# Baseband.net
KiCad netlist of a schematic drawn in Altium Designer
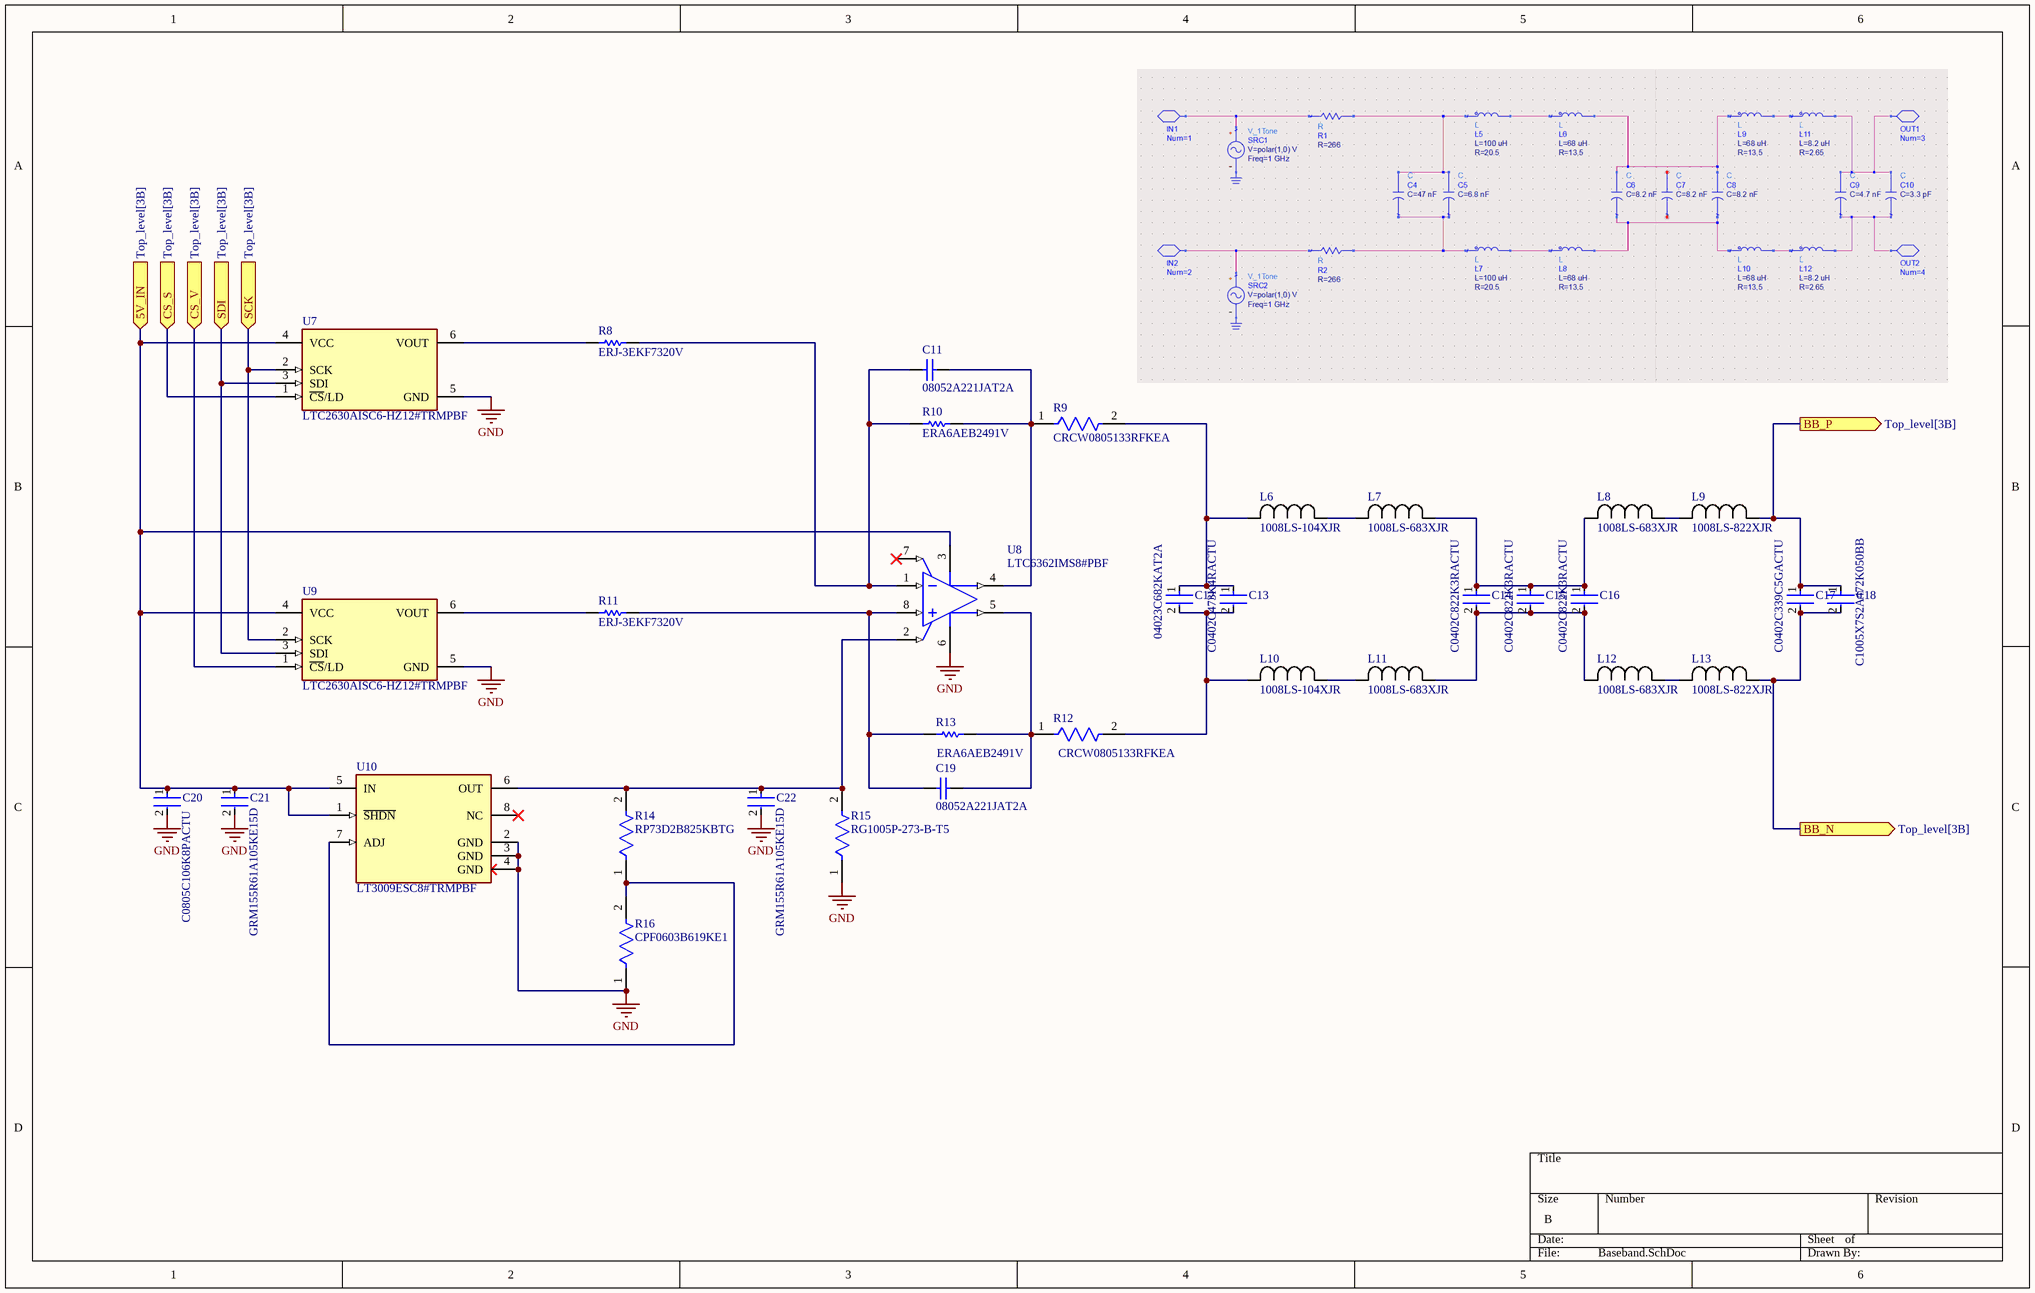
[diagram p0: Baseband.SchDoc]

(export (version "E")
  (design (tool "Eeschema 10.0.6"))
  (components
    (comp (ref "C11")
      (value "08052A221JAT2A")
      (footprint "CAPC2013X140X50LL20T25")
      (fields (field (name "MANUFACTURER") "AVX Interconnect / Elco"))
      (libsource (lib "Altium Content Vault") (part "CAP"))
    )
    (comp (ref "C12")
      (value "04023C682KAT2A")
      (footprint "FP-0402-L_1_0_1-W_0_5_0_1-IPC_A")
      (description "General Purpose Ceramic Capacitor, 0402, 6.8nF, 10%, X7R, 15%, 25V")
      (fields (field (name "TOLERANCE") "10%") (field (name "VOLTAGE") "25V"))
      (libsource (lib "Altium Content Vault") (part "b4654b650e69147ec39a6b967a45e02"))
    )
    (comp (ref "C13")
      (value "C0402C473K4RACTU")
      (footprint "FP-C0402-BB-MFG")
      (description "Cap Ceramic 0.047uF 16V X7R 10% SMD 0402 125°C Paper T/R")
      (fields (field (name "TOLERANCE") "0.1") (field (name "MANUFACTURER") "Kemet"))
      (libsource (lib "Altium Content Vault") (part "b4654b650e69147ec39a6b967a45e02"))
    )
    (comp (ref "C14")
      (value "C0402C822K3RACTU")
      (footprint "FP-C0402-BB-MFG")
      (description "CAP CER 8200PF 25V X7R 0402")
      (fields (field (name "TOLERANCE") "0.1") (field (name "MANUFACTURER") "Kemet"))
      (libsource (lib "Altium Content Vault") (part "b4654b650e69147ec39a6b967a45e02"))
    )
    (comp (ref "C15")
      (value "C0402C822K3RACTU")
      (footprint "FP-C0402-BB-MFG")
      (description "CAP CER 8200PF 25V X7R 0402")
      (fields (field (name "TOLERANCE") "0.1") (field (name "MANUFACTURER") "Kemet"))
      (libsource (lib "Altium Content Vault") (part "b4654b650e69147ec39a6b967a45e02"))
    )
    (comp (ref "C16")
      (value "C0402C822K3RACTU")
      (footprint "FP-C0402-BB-MFG")
      (description "CAP CER 8200PF 25V X7R 0402")
      (fields (field (name "TOLERANCE") "0.1") (field (name "MANUFACTURER") "Kemet"))
      (libsource (lib "Altium Content Vault") (part "b4654b650e69147ec39a6b967a45e02"))
    )
    (comp (ref "C17")
      (value "C1005X7S2A472K050BB")
      (footprint "FP-C1005-050-0_05-IPC_C")
      (description "Multilayer Ceramic Capacitors 4.7nF ±10% 100V X7S SMD 0402")
      (fields (field (name "TOLERANCE") "10%"))
      (libsource (lib "Altium Content Vault") (part "b4654b650e69147ec39a6b967a45e02"))
    )
    (comp (ref "C18")
      (value "C0402C339C5GACTU")
      (footprint "FP-C0402-BB-MFG")
      (description "Capacitor: ceramic; MLCC; 3.3pF; 50VDC; C0G; ±0.25pF; SMD; 0402")
      (fields (field (name "TOLERANCE") "0.25 pF") (field (name "MANUFACTURER") "Kemet"))
      (libsource (lib "Altium Content Vault") (part "b4654b650e69147ec39a6b967a45e02"))
    )
    (comp (ref "C19")
      (value "08052A221JAT2A")
      (footprint "CAPC2013X140X50LL20T25")
      (fields (field (name "MANUFACTURER") "AVX Interconnect / Elco"))
      (libsource (lib "Altium Content Vault") (part "CAP"))
    )
    (comp (ref "C20")
      (value "C0805C106K8PACTU")
      (footprint "FP-C0805C-DG-MFG")
      (description "CAP CER 10UF 10V X5R 0805")
      (fields (field (name "TOLERANCE") "10%") (field (name "MANUFACTURER") "Kemet"))
      (libsource (lib "Altium Content Vault") (part "11868f565c42a9108669ba33697ecf6"))
    )
    (comp (ref "C21")
      (value "GRM155R61A105KE15D")
      (footprint "FP-GRM15-0_1-MFG")
      (description "CAP CER 1UF 10V X5R 0402")
      (fields
        (field (name "OCTOPART") "https://octopart.com/grm155r61a105ke15d-murata-197442")
        (field (name "MANUFACTURER") "Murata")
      )
      (libsource (lib "Altium Content Vault") (part "02cd4be3c70576c341d710602a673aa"))
    )
    (comp (ref "C22")
      (value "GRM155R61A105KE15D")
      (footprint "FP-GRM15-0_1-MFG")
      (description "CAP CER 1UF 10V X5R 0402")
      (fields
        (field (name "OCTOPART") "https://octopart.com/grm155r61a105ke15d-murata-197442")
        (field (name "MANUFACTURER") "Murata")
      )
      (libsource (lib "Altium Content Vault") (part "02cd4be3c70576c341d710602a673aa"))
    )
    (comp (ref "L6")
      (value "1008LS-104XJR")
      (footprint "IND_1008LS")
      (description "No Description Available")
      (fields
        (field (name "MANUFACTURER_PART_NUMBER") "1008LS-152XJLC")
        (field (name "COPYRIGHT") "Copyright (C) 2023 Ultra Librarian. All rights reserved.")
      )
      (libsource (lib "1008LS-152XJLC") (part "1008LS-152XJLC"))
    )
    (comp (ref "L7")
      (value "1008LS-683XJR")
      (footprint "IND_1008LS")
      (description "No Description Available")
      (fields
        (field (name "MANUFACTURER_PART_NUMBER") "1008LS-152XJLC")
        (field (name "COPYRIGHT") "Copyright (C) 2023 Ultra Librarian. All rights reserved.")
      )
      (libsource (lib "1008LS-152XJLC") (part "1008LS-152XJLC"))
    )
    (comp (ref "L8")
      (value "1008LS-683XJR")
      (footprint "IND_1008LS")
      (description "No Description Available")
      (fields
        (field (name "MANUFACTURER_PART_NUMBER") "1008LS-152XJLC")
        (field (name "COPYRIGHT") "Copyright (C) 2023 Ultra Librarian. All rights reserved.")
      )
      (libsource (lib "1008LS-152XJLC") (part "1008LS-152XJLC"))
    )
    (comp (ref "L9")
      (value "1008LS-822XJR")
      (footprint "IND_1008LS")
      (description "No Description Available")
      (fields
        (field (name "MANUFACTURER_PART_NUMBER") "1008LS-152XJLC")
        (field (name "COPYRIGHT") "Copyright (C) 2023 Ultra Librarian. All rights reserved.")
      )
      (libsource (lib "1008LS-152XJLC") (part "1008LS-152XJLC"))
    )
    (comp (ref "L10")
      (value "1008LS-104XJR")
      (footprint "IND_1008LS")
      (description "No Description Available")
      (fields
        (field (name "MANUFACTURER_PART_NUMBER") "1008LS-152XJLC")
        (field (name "COPYRIGHT") "Copyright (C) 2023 Ultra Librarian. All rights reserved.")
      )
      (libsource (lib "1008LS-152XJLC") (part "1008LS-152XJLC"))
    )
    (comp (ref "L11")
      (value "1008LS-683XJR")
      (footprint "IND_1008LS")
      (description "No Description Available")
      (fields
        (field (name "MANUFACTURER_PART_NUMBER") "1008LS-152XJLC")
        (field (name "COPYRIGHT") "Copyright (C) 2023 Ultra Librarian. All rights reserved.")
      )
      (libsource (lib "1008LS-152XJLC") (part "1008LS-152XJLC"))
    )
    (comp (ref "L12")
      (value "1008LS-683XJR")
      (footprint "IND_1008LS")
      (description "No Description Available")
      (fields
        (field (name "MANUFACTURER_PART_NUMBER") "1008LS-152XJLC")
        (field (name "COPYRIGHT") "Copyright (C) 2023 Ultra Librarian. All rights reserved.")
      )
      (libsource (lib "1008LS-152XJLC") (part "1008LS-152XJLC"))
    )
    (comp (ref "L13")
      (value "1008LS-822XJR")
      (footprint "IND_1008LS")
      (description "No Description Available")
      (fields
        (field (name "MANUFACTURER_PART_NUMBER") "1008LS-152XJLC")
        (field (name "COPYRIGHT") "Copyright (C) 2023 Ultra Librarian. All rights reserved.")
      )
      (libsource (lib "1008LS-152XJLC") (part "1008LS-152XJLC"))
    )
    (comp (ref "R8")
      (value "ERJ-3EKF7320V")
      (footprint "RESC1608X55X30LL15T15")
      (fields (field (name "MANUFACTURER") "Panasonic"))
      (libsource (lib "Altium Content Vault") (part "RES"))
    )
    (comp (ref "R9")
      (value "CRCW0805133RFKEA")
      (footprint "FP-CRCW0805-e3-IPC_C")
      (description "RES Thick Film, 133Ω, 1%, 0.125W, 100ppm/°C, 0805")
      (fields (field (name "TOLERANCE") "1%"))
      (libsource (lib "Altium Content Vault") (part "1029c3af85768c4190bb7ad29bc67b5"))
    )
    (comp (ref "R10")
      (value "ERA6AEB2491V")
      (footprint "RESC2013X60X40LL20T25")
      (fields (field (name "MANUFACTURER") "Panasonic"))
      (libsource (lib "Altium Content Vault") (part "RES"))
    )
    (comp (ref "R11")
      (value "ERJ-3EKF7320V")
      (footprint "RESC1608X55X30LL15T15")
      (fields (field (name "MANUFACTURER") "Panasonic"))
      (libsource (lib "Altium Content Vault") (part "RES"))
    )
    (comp (ref "R12")
      (value "CRCW0805133RFKEA")
      (footprint "FP-CRCW0805-e3-IPC_C")
      (description "RES Thick Film, 133Ω, 1%, 0.125W, 100ppm/°C, 0805")
      (fields (field (name "TOLERANCE") "1%"))
      (libsource (lib "Altium Content Vault") (part "1029c3af85768c4190bb7ad29bc67b5"))
    )
    (comp (ref "R13")
      (value "ERA6AEB2491V")
      (footprint "RESC2013X60X40LL20T25")
      (fields (field (name "MANUFACTURER") "Panasonic"))
      (libsource (lib "Altium Content Vault") (part "RES"))
    )
    (comp (ref "R14")
      (value "RP73D2B825KBTG")
      (footprint "FP-RP732B-MFG")
      (description "Res Thin Film 1206 825KΩ 0.1% 0.25W 15ppm/°C Molded SMD")
      (fields
        (field (name "TOLERANCE") "0.1%")
        (field (name "OCTOPART") "https://octopart.com/rp73d2b825kbtg-te+connectivity-42012325")
      )
      (libsource (lib "Altium Content Vault") (part "1029c3af85768c4190bb7ad29bc67b5"))
    )
    (comp (ref "R15")
      (value "RG1005P-273-B-T5")
      (footprint "FP-RG1005-IPC_B")
      (description "Automotive Metal Thin Film Chip Resistor, 0402, 27kΩ, 0.1%, 25ppm/°C, 0.0625W, 75V")
      (fields (field (name "TOLERANCE") "0.1%"))
      (libsource (lib "Altium Content Vault") (part "1029c3af85768c4190bb7ad29bc67b5"))
    )
    (comp (ref "R16")
      (value "CPF0603B619KE1")
      (footprint "FP-CPF0603-MFG")
      (description "RES SMD 619KΩ 0.1% 1/16W 0603")
      (fields (field (name "TOLERANCE") "0.1%") (field (name "MANUFACTURER") "TE Connectivity"))
      (libsource (lib "Altium Content Vault") (part "1029c3af85768c4190bb7ad29bc67b5"))
    )
    (comp (ref "U7")
      (value "LTC2630AISC6-HZ12#TRMPBF")
      (footprint "FP-SC6-6-05-08-1638-IPC_A")
      (description "IC DAC 12BIT V-OUT SC70-6")
      (libsource (lib "Altium Content Vault") (part "11e261d70a0233db44de8961138878f"))
    )
    (comp (ref "U8")
      (value "LTC6362IMS8#PBF")
      (footprint "LT-MS8-8_L")
      (fields
        (field (name "MANUFACTURER") "Linear Technology")
        (field (name "LINEAR TECHNOLOGY PART NUMBER") "LTC6362")
      )
      (libsource (lib "Altium Content Vault") (part "LT-LTC6362-MS8-8"))
    )
    (comp (ref "U9")
      (value "LTC2630AISC6-HZ12#TRMPBF")
      (footprint "FP-SC6-6-05-08-1638-IPC_A")
      (description "IC DAC 12BIT V-OUT SC70-6")
      (libsource (lib "Altium Content Vault") (part "11e261d70a0233db44de8961138878f"))
    )
    (comp (ref "U10")
      (value "LT3009ESC8#TRMPBF")
      (footprint "FP-SC8-8-05-08-1639-MFG")
      (description "IC REG LIN POS ADJ 20MA SC70-8")
      (libsource (lib "Altium Content Vault") (part "448a231521b8ff0e769f98827e76e85"))
    )
  )
  (nets
    (net (code "1") (name "/5V_IN") (class "Default")
      (node (ref "C20") (pin "1") (pinfunction "1_1") (pintype "passive"))
      (node (ref "C21") (pin "1") (pinfunction "1_1") (pintype "passive"))
      (node (ref "U10") (pin "1") (pinfunction "~{SHDN}_1") (pintype "input"))
      (node (ref "U10") (pin "5") (pinfunction "IN_5") (pintype "power_in"))
      (node (ref "U7") (pin "4") (pinfunction "VCC_4") (pintype "power_in"))
      (node (ref "U8") (pin "3") (pinfunction "V+_3") (pintype "power_in"))
      (node (ref "U9") (pin "4") (pinfunction "VCC_4") (pintype "power_in"))
    )
    (net (code "2") (name "/BB_N") (class "Default")
      (node (ref "C17") (pin "2") (pinfunction "2_2") (pintype "passive"))
      (node (ref "C18") (pin "2") (pinfunction "2_2") (pintype "passive"))
      (node (ref "L13") (pin "1") (pinfunction "1_1") (pintype "passive"))
    )
    (net (code "3") (name "/BB_P") (class "Default")
      (node (ref "C17") (pin "1") (pinfunction "1_1") (pintype "passive"))
      (node (ref "C18") (pin "1") (pinfunction "1_1") (pintype "passive"))
      (node (ref "L9") (pin "1") (pinfunction "1_1") (pintype "passive"))
    )
    (net (code "4") (name "/CS_S") (class "Default")
      (node (ref "U7") (pin "1") (pinfunction "~{CS}/LD_1") (pintype "input"))
    )
    (net (code "5") (name "/CS_V") (class "Default")
      (node (ref "U9") (pin "1") (pinfunction "~{CS}/LD_1") (pintype "input"))
    )
    (net (code "6") (name "/SCK") (class "Default")
      (node (ref "U7") (pin "2") (pinfunction "SCK_2") (pintype "input"))
      (node (ref "U9") (pin "2") (pinfunction "SCK_2") (pintype "input"))
    )
    (net (code "7") (name "/SDI") (class "Default")
      (node (ref "U7") (pin "3") (pinfunction "SDI_3") (pintype "input"))
      (node (ref "U9") (pin "3") (pinfunction "SDI_3") (pintype "input"))
    )
    (net (code "8") (name "GND") (class "Default")
      (node (ref "C20") (pin "2") (pinfunction "2_2") (pintype "passive"))
      (node (ref "C21") (pin "2") (pinfunction "2_2") (pintype "passive"))
      (node (ref "C22") (pin "2") (pinfunction "2_2") (pintype "passive"))
      (node (ref "R15") (pin "1") (pinfunction "1_1") (pintype "passive"))
      (node (ref "R16") (pin "1") (pinfunction "1_1") (pintype "passive"))
      (node (ref "U10") (pin "2") (pinfunction "GND_2") (pintype "power_in"))
      (node (ref "U10") (pin "3") (pinfunction "GND_3") (pintype "power_in"))
      (node (ref "U10") (pin "4") (pinfunction "GND_4") (pintype "power_in"))
      (node (ref "U7") (pin "5") (pinfunction "GND_5") (pintype "power_in"))
      (node (ref "U8") (pin "6") (pinfunction "V-_6") (pintype "power_in"))
      (node (ref "U9") (pin "5") (pinfunction "GND_5") (pintype "power_in"))
    )
    (net (code "9") (name "Net-(C12-Pad1)") (class "Default")
      (node (ref "C12") (pin "1") (pinfunction "1_1") (pintype "passive"))
      (node (ref "C13") (pin "1") (pinfunction "1_1") (pintype "passive"))
      (node (ref "L6") (pin "2") (pinfunction "2_2") (pintype "passive"))
      (node (ref "R9") (pin "2") (pinfunction "2_2") (pintype "passive"))
    )
    (net (code "10") (name "Net-(C12-Pad2)") (class "Default")
      (node (ref "C12") (pin "2") (pinfunction "2_2") (pintype "passive"))
      (node (ref "C13") (pin "2") (pinfunction "2_2") (pintype "passive"))
      (node (ref "L10") (pin "2") (pinfunction "2_2") (pintype "passive"))
      (node (ref "R12") (pin "2") (pinfunction "2_2") (pintype "passive"))
    )
    (net (code "11") (name "Net-(C14-Pad1)") (class "Default")
      (node (ref "C14") (pin "1") (pinfunction "1_1") (pintype "passive"))
      (node (ref "C15") (pin "1") (pinfunction "1_1") (pintype "passive"))
      (node (ref "C16") (pin "1") (pinfunction "1_1") (pintype "passive"))
      (node (ref "L7") (pin "1") (pinfunction "1_1") (pintype "passive"))
      (node (ref "L8") (pin "2") (pinfunction "2_2") (pintype "passive"))
    )
    (net (code "12") (name "Net-(C14-Pad2)") (class "Default")
      (node (ref "C14") (pin "2") (pinfunction "2_2") (pintype "passive"))
      (node (ref "C15") (pin "2") (pinfunction "2_2") (pintype "passive"))
      (node (ref "C16") (pin "2") (pinfunction "2_2") (pintype "passive"))
      (node (ref "L11") (pin "1") (pinfunction "1_1") (pintype "passive"))
      (node (ref "L12") (pin "2") (pinfunction "2_2") (pintype "passive"))
    )
    (net (code "13") (name "Net-(L6-Pad1)") (class "Default")
      (node (ref "L6") (pin "1") (pinfunction "1_1") (pintype "passive"))
      (node (ref "L7") (pin "2") (pinfunction "2_2") (pintype "passive"))
    )
    (net (code "14") (name "Net-(L8-Pad1)") (class "Default")
      (node (ref "L8") (pin "1") (pinfunction "1_1") (pintype "passive"))
      (node (ref "L9") (pin "2") (pinfunction "2_2") (pintype "passive"))
    )
    (net (code "15") (name "Net-(L10-Pad1)") (class "Default")
      (node (ref "L10") (pin "1") (pinfunction "1_1") (pintype "passive"))
      (node (ref "L11") (pin "2") (pinfunction "2_2") (pintype "passive"))
    )
    (net (code "16") (name "Net-(L12-Pad1)") (class "Default")
      (node (ref "L12") (pin "1") (pinfunction "1_1") (pintype "passive"))
      (node (ref "L13") (pin "2") (pinfunction "2_2") (pintype "passive"))
    )
    (net (code "17") (name "Net-(U7-VOUT)") (class "Default")
      (node (ref "R8") (pin "1") (pinfunction "1_1") (pintype "passive"))
      (node (ref "U7") (pin "6") (pinfunction "VOUT_6") (pintype "passive"))
    )
    (net (code "18") (name "Net-(U8-+IN)") (class "Default")
      (node (ref "C19") (pin "1") (pinfunction "1_1") (pintype "passive"))
      (node (ref "R11") (pin "2") (pinfunction "2_2") (pintype "passive"))
      (node (ref "R13") (pin "1") (pinfunction "1_1") (pintype "passive"))
      (node (ref "U8") (pin "8") (pinfunction "+IN_8") (pintype "input"))
    )
    (net (code "19") (name "Net-(U8-+OUT)") (class "Default")
      (node (ref "C11") (pin "2") (pinfunction "2_2") (pintype "passive"))
      (node (ref "R10") (pin "2") (pinfunction "2_2") (pintype "passive"))
      (node (ref "R9") (pin "1") (pinfunction "1_1") (pintype "passive"))
      (node (ref "U8") (pin "4") (pinfunction "+OUT_4") (pintype "output"))
    )
    (net (code "20") (name "Net-(U8--IN)") (class "Default")
      (node (ref "C11") (pin "1") (pinfunction "1_1") (pintype "passive"))
      (node (ref "R10") (pin "1") (pinfunction "1_1") (pintype "passive"))
      (node (ref "R8") (pin "2") (pinfunction "2_2") (pintype "passive"))
      (node (ref "U8") (pin "1") (pinfunction "-IN_1") (pintype "input"))
    )
    (net (code "21") (name "Net-(U8--OUT)") (class "Default")
      (node (ref "C19") (pin "2") (pinfunction "2_2") (pintype "passive"))
      (node (ref "R12") (pin "1") (pinfunction "1_1") (pintype "passive"))
      (node (ref "R13") (pin "2") (pinfunction "2_2") (pintype "passive"))
      (node (ref "U8") (pin "5") (pinfunction "-OUT_5") (pintype "output"))
    )
    (net (code "22") (name "Net-(U9-VOUT)") (class "Default")
      (node (ref "R11") (pin "1") (pinfunction "1_1") (pintype "passive"))
      (node (ref "U9") (pin "6") (pinfunction "VOUT_6") (pintype "passive"))
    )
    (net (code "23") (name "Net-(U10-ADJ)") (class "Default")
      (node (ref "R14") (pin "1") (pinfunction "1_1") (pintype "passive"))
      (node (ref "R16") (pin "2") (pinfunction "2_2") (pintype "passive"))
      (node (ref "U10") (pin "7") (pinfunction "ADJ_7") (pintype "input"))
    )
    (net (code "24") (name "Net-(U10-OUT)") (class "Default")
      (node (ref "C22") (pin "1") (pinfunction "1_1") (pintype "passive"))
      (node (ref "R14") (pin "2") (pinfunction "2_2") (pintype "passive"))
      (node (ref "R15") (pin "2") (pinfunction "2_2") (pintype "passive"))
      (node (ref "U10") (pin "6") (pinfunction "OUT_6") (pintype "power_in"))
      (node (ref "U8") (pin "2") (pinfunction "VOCM_2") (pintype "input"))
    )
    (net (code "25") (name "unconnected-(U8-~{SHDN}-Pad7)") (class "Default")
      (node (ref "U8") (pin "7") (pinfunction "~{SHDN}_7") (pintype "input+no_connect"))
    )
    (net (code "26") (name "unconnected-(U10-NC-Pad8)") (class "Default")
      (node (ref "U10") (pin "8") (pinfunction "NC_8") (pintype "passive+no_connect"))
    )
  )
)
